# Manette.net
KiCad netlist of a schematic drawn in Altium Designer
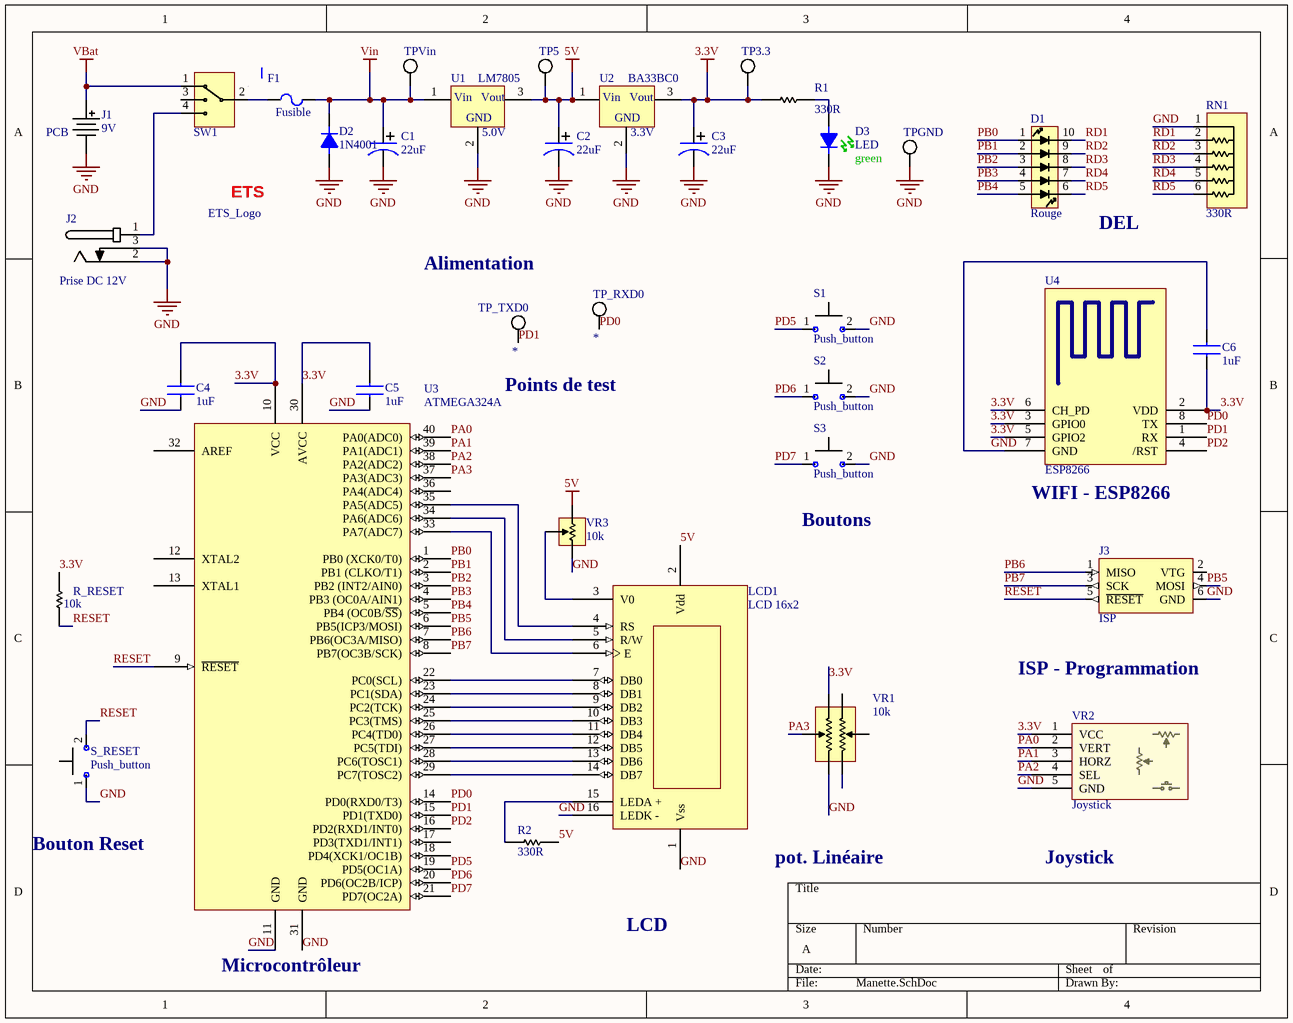
[diagram p0: Manette.SchDoc]

(export (version "E")
  (design (tool "Eeschema 10.0.6"))
  (components
    (comp (ref "C1")
      (value "22uF")
      (footprint "Cap Pol (100mil, 80mil)")
      (description "Capacitor")
      (libsource (lib "Condensateur") (part "Electrolytique"))
    )
    (comp (ref "C2")
      (value "22uF")
      (footprint "Cap Pol (100mil, 80mil)")
      (description "Capacitor")
      (libsource (lib "Condensateur") (part "Electrolytique"))
    )
    (comp (ref "C3")
      (value "22uF")
      (footprint "Cap Pol (100mil, 80mil)")
      (description "Capacitor")
      (libsource (lib "Condensateur") (part "Electrolytique"))
    )
    (comp (ref "C4")
      (value "1uF")
      (footprint "Cap UNPOL (200mil, 80mil)")
      (description "Capacitor")
      (libsource (lib "Condensateur") (part "Ceramique"))
    )
    (comp (ref "C5")
      (value "1uF")
      (footprint "Cap UNPOL (200mil, 80mil)")
      (description "Capacitor")
      (libsource (lib "Condensateur") (part "Ceramique"))
    )
    (comp (ref "C6")
      (value "1uF")
      (footprint "Cap UNPOL (200mil, 80mil)")
      (description "Capacitor")
      (libsource (lib "Condensateur") (part "Ceramique"))
    )
    (comp (ref "D1")
      (value "Rouge")
      (footprint "BARGRAPH 5 DEL")
      (description "Bargraph 5 DEL")
      (libsource (lib "DEL") (part "Bargraph 5 DEL"))
    )
    (comp (ref "D2")
      (value "1N4001")
      (footprint "DO-41 (AN) 400mil")
      (description "Diode 1N4001")
      (libsource (lib "Diode") (part "1N4001"))
    )
    (comp (ref "D3")
      (value "LED")
      (footprint "LED_GREEN_5mm-100mil")
      (description "DEL verte 5mm (translucide)")
      (fields (field (name "COLOR") "green"))
      (libsource (lib "DEL") (part "LED_verte"))
    )
    (comp (ref "F1") (value "Fuse") (footprint "Fuse") (libsource (lib "Fusible") (part "Fuse")))
    (comp (ref "J1")
      (value "9V")
      (footprint "9V PCB Through hole")
      (description "9V PCB battery holder through hole")
      (fields (field (name "Comment") "9 VPCB through hole"))
      (libsource (lib "Batterie") (part "9 VPCB through hole"))
    )
    (comp (ref "J2")
      (value "Prise DC 12V")
      (footprint "Prise DC 12V")
      (libsource (lib "PriseDC12V") (part "Prise DC 12V"))
    )
    (comp (ref "J3")
      (value "ISP")
      (footprint "ISP 2x3 avec detrompeur")
      (description "Connecteur ISP 2x3")
      (libsource (lib "Connecteur-Male") (part "ISP 2x3"))
    )
    (comp (ref "LCD1")
      (value "LCD 16x2")
      (footprint "LCD 16x2 sans socket")
      (description "Écran LCD compatible HD44780")
      (libsource (lib "Ecran LCD") (part "LCD 16x2"))
    )
    (comp (ref "R1")
      (value "330R")
      (footprint "Resistor 330 (400mils)")
      (description "Resistor 330R")
      (libsource (lib "Resistance") (part "Resistor 330R"))
    )
    (comp (ref "R2")
      (value "330R")
      (footprint "Resistor 330 (400mils)")
      (description "Resistor 330R")
      (libsource (lib "Resistance") (part "Resistor 330R"))
    )
    (comp (ref "RN1")
      (value "330R")
      (footprint "RESEAU 5 RESISTANCES")
      (description "Réseau de 5 résistances pour bus")
      (fields (field (name "Comment") "Réseau de 5 résistances"))
      (libsource (lib "Resistance") (part "Réseau de 5 résistances"))
    )
    (comp (ref "R_RESET")
      (value "10k")
      (footprint "Resistor 10k (400mils)")
      (description "Résistor 10k")
      (libsource (lib "Resistance") (part "Resistor 10k"))
    )
    (comp (ref "S1")
      (value "Push_button")
      (footprint "MJTP1230")
      (description "Bouton poussoir tactile")
      (libsource (lib "Interrupteur") (part "Push_button"))
    )
    (comp (ref "S2")
      (value "Push_button")
      (footprint "MJTP1230")
      (description "Bouton poussoir tactile")
      (libsource (lib "Interrupteur") (part "Push_button"))
    )
    (comp (ref "S3")
      (value "Push_button")
      (footprint "MJTP1230")
      (description "Bouton poussoir tactile")
      (libsource (lib "Interrupteur") (part "Push_button"))
    )
    (comp (ref "SS1") (value "ETS_Logo") (footprint "ETS-Logo") (libsource (lib "LogoETS") (part "ETS_Logo")))
    (comp (ref "SW1")
      (value "1825161-1")
      (footprint "1825161-1")
      (description "Interrupteur SP3T à glissière")
      (libsource (lib "Interrupteur") (part "1825161-1"))
    )
    (comp (ref "S_RESET")
      (value "Push_button")
      (footprint "MJTP1230")
      (description "Bouton poussoir tactile")
      (libsource (lib "Interrupteur") (part "Push_button"))
    )
    (comp (ref "TP3.3")
      (value "*")
      (footprint "HEADER MALE 1X1")
      (description "Point de test")
      (libsource (lib "Connecteur-Male") (part "Test point"))
    )
    (comp (ref "TP5")
      (value "*")
      (footprint "HEADER MALE 1X1")
      (description "Point de test")
      (libsource (lib "Connecteur-Male") (part "Test point"))
    )
    (comp (ref "TPGND")
      (value "*")
      (footprint "HEADER MALE 1X1")
      (description "Point de test")
      (libsource (lib "Connecteur-Male") (part "Test point"))
    )
    (comp (ref "TPVin")
      (value "*")
      (footprint "HEADER MALE 1X1")
      (description "Point de test")
      (libsource (lib "Connecteur-Male") (part "Test point"))
    )
    (comp (ref "TP_RXD0")
      (value "*")
      (footprint "HEADER MALE 1X1")
      (description "Point de test")
      (fields (field (name "ALTIUM_VALUE") "*"))
      (libsource (lib "Connecteur-Male") (part "Test point"))
    )
    (comp (ref "TP_TXD0")
      (value "*")
      (footprint "HEADER MALE 1X1")
      (description "Point de test")
      (fields (field (name "ALTIUM_VALUE") "*"))
      (libsource (lib "Connecteur-Male") (part "Test point"))
    )
    (comp (ref "U1")
      (value "LM7805")
      (footprint "TO-220FP-3")
      (description "Régulateur de tension 5V")
      (libsource (lib "Convertisseur Tension") (part "LM7805"))
    )
    (comp (ref "U2")
      (value "BA33BC0")
      (footprint "TO-220FP-3")
      (description "LDO 3.3V, 1A, 0.3V@200mA, up to 16V (BA33BC0)")
      (libsource (lib "Convertisseur Tension") (part "LDO 3.3V"))
    )
    (comp (ref "U3")
      (value "ATMEGA324A")
      (footprint "ATMEGA324A-DIP")
      (description "Microcontrôleur ATmega324A avec 32K de flash")
      (libsource (lib "Microcontroleur") (part "ATMEGA324A"))
    )
    (comp (ref "U4") (value "ESP8266") (footprint "ESP8266") (libsource (lib "ESP8266") (part "ESP8266")))
    (comp (ref "VR1")
      (value "10k")
      (footprint "PS45M-0MC2BR10KN")
      (description "Potentiomètre à glissière double 10k")
      (libsource (lib "Potentiometre") (part "PS45M-0MC2BR10KN"))
    )
    (comp (ref "VR2")
      (value "Joystick")
      (footprint "JOYSTICK SUR BREAKOUT&SOCKET")
      (description "2 axes thumb joystick avec bouton")
      (libsource (lib "Joystick") (part "Joystick"))
    )
    (comp (ref "VR3")
      (value "10k")
      (footprint "Trimpot")
      (description "Potentiomètre linéaire")
      (fields (field (name "Comment") "Trimpot"))
      (libsource (lib "Potentiometre") (part "Trimpot"))
    )
  )
  (nets
    (net (code "1") (name "/PA0") (class "Default")
      (node (ref "U3") (pin "40") (pinfunction "PA0(ADC0)_40") (pintype "bidirectional"))
      (node (ref "VR2") (pin "2") (pinfunction "VERT_2") (pintype "passive"))
    )
    (net (code "2") (name "/PA1") (class "Default")
      (node (ref "U3") (pin "39") (pinfunction "PA1(ADC1)_39") (pintype "bidirectional"))
      (node (ref "VR2") (pin "3") (pinfunction "HORZ_3") (pintype "passive"))
    )
    (net (code "3") (name "/PA2") (class "Default")
      (node (ref "U3") (pin "38") (pinfunction "PA2(ADC2)_38") (pintype "bidirectional"))
      (node (ref "VR2") (pin "4") (pinfunction "SEL_4") (pintype "passive"))
    )
    (net (code "4") (name "/PA3") (class "Default")
      (node (ref "U3") (pin "37") (pinfunction "PA3(ADC3)_37") (pintype "bidirectional"))
      (node (ref "VR1") (pin "2") (pinfunction "V_2") (pintype "passive"))
    )
    (net (code "5") (name "/PB0") (class "Default")
      (node (ref "D1") (pin "1") (pinfunction "A1_1") (pintype "passive"))
      (node (ref "U3") (pin "1") (pinfunction "PB0_(XCK0/T0)_1") (pintype "bidirectional"))
    )
    (net (code "6") (name "/PB1") (class "Default")
      (node (ref "D1") (pin "2") (pinfunction "A2_2") (pintype "passive"))
      (node (ref "U3") (pin "2") (pinfunction "PB1_(CLKO/T1)_2") (pintype "bidirectional"))
    )
    (net (code "7") (name "/PB2") (class "Default")
      (node (ref "D1") (pin "3") (pinfunction "A3_3") (pintype "passive"))
      (node (ref "U3") (pin "3") (pinfunction "PB2_(INT2/AIN0)_3") (pintype "bidirectional"))
    )
    (net (code "8") (name "/PB3") (class "Default")
      (node (ref "D1") (pin "4") (pinfunction "A4_4") (pintype "passive"))
      (node (ref "U3") (pin "4") (pinfunction "PB3_(OC0A/AIN1)_4") (pintype "bidirectional"))
    )
    (net (code "9") (name "/PB4") (class "Default")
      (node (ref "D1") (pin "5") (pinfunction "A5_5") (pintype "passive"))
      (node (ref "U3") (pin "5") (pinfunction "PB4_(OC0B/~{SS})_5") (pintype "bidirectional"))
    )
    (net (code "10") (name "/PB5") (class "Default")
      (node (ref "J3") (pin "4") (pinfunction "MOSI_4") (pintype "output"))
      (node (ref "U3") (pin "6") (pinfunction "PB5(ICP3/MOSI)_6") (pintype "bidirectional"))
    )
    (net (code "11") (name "/PB6") (class "Default")
      (node (ref "J3") (pin "1") (pinfunction "MISO_1") (pintype "input"))
      (node (ref "U3") (pin "7") (pinfunction "PB6(OC3A/MISO)_7") (pintype "bidirectional"))
    )
    (net (code "12") (name "/PB7") (class "Default")
      (node (ref "J3") (pin "3") (pinfunction "SCK_3") (pintype "output"))
      (node (ref "U3") (pin "8") (pinfunction "PB7(OC3B/SCK)_8") (pintype "bidirectional"))
    )
    (net (code "13") (name "/PD0") (class "Default")
      (node (ref "TP_RXD0") (pin "1") (pinfunction "1_1") (pintype "passive"))
      (node (ref "U3") (pin "14") (pinfunction "PD0(RXD0/T3)_14") (pintype "bidirectional"))
      (node (ref "U4") (pin "8") (pinfunction "TX_8") (pintype "passive"))
    )
    (net (code "14") (name "/PD1") (class "Default")
      (node (ref "TP_TXD0") (pin "1") (pinfunction "1_1") (pintype "passive"))
      (node (ref "U3") (pin "15") (pinfunction "PD1(TXD0)_15") (pintype "bidirectional"))
      (node (ref "U4") (pin "1") (pinfunction "RX_1") (pintype "passive"))
    )
    (net (code "15") (name "/PD2") (class "Default")
      (node (ref "U3") (pin "16") (pinfunction "PD2(RXD1/INT0)_16") (pintype "bidirectional"))
      (node (ref "U4") (pin "4") (pinfunction "/RST_4") (pintype "passive"))
    )
    (net (code "16") (name "/PD5") (class "Default")
      (node (ref "S1") (pin "1") (pintype "passive"))
      (node (ref "U3") (pin "19") (pinfunction "PD5(OC1A)_19") (pintype "bidirectional"))
    )
    (net (code "17") (name "/PD6") (class "Default")
      (node (ref "S2") (pin "1") (pintype "passive"))
      (node (ref "U3") (pin "20") (pinfunction "PD6(OC2B/ICP)_20") (pintype "bidirectional"))
    )
    (net (code "18") (name "/PD7") (class "Default")
      (node (ref "S3") (pin "1") (pintype "passive"))
      (node (ref "U3") (pin "21") (pinfunction "PD7(OC2A)_21") (pintype "bidirectional"))
    )
    (net (code "19") (name "/RD1") (class "Default")
      (node (ref "D1") (pin "10") (pinfunction "K1_10") (pintype "passive"))
      (node (ref "RN1") (pin "2") (pinfunction "R1_2") (pintype "passive"))
    )
    (net (code "20") (name "/RD2") (class "Default")
      (node (ref "D1") (pin "9") (pinfunction "K2_9") (pintype "passive"))
      (node (ref "RN1") (pin "3") (pinfunction "R2_3") (pintype "passive"))
    )
    (net (code "21") (name "/RD3") (class "Default")
      (node (ref "D1") (pin "8") (pinfunction "K3_8") (pintype "passive"))
      (node (ref "RN1") (pin "4") (pinfunction "R3_4") (pintype "passive"))
    )
    (net (code "22") (name "/RD4") (class "Default")
      (node (ref "D1") (pin "7") (pinfunction "K4_7") (pintype "passive"))
      (node (ref "RN1") (pin "5") (pinfunction "R4_5") (pintype "passive"))
    )
    (net (code "23") (name "/RD5") (class "Default")
      (node (ref "D1") (pin "6") (pinfunction "K5_6") (pintype "passive"))
      (node (ref "RN1") (pin "6") (pinfunction "R5_6") (pintype "passive"))
    )
    (net (code "24") (name "/RESET") (class "Default")
      (node (ref "J3") (pin "5") (pinfunction "~{RESET}_5") (pintype "output"))
      (node (ref "R_RESET") (pin "1") (pinfunction "1_1") (pintype "passive"))
      (node (ref "S_RESET") (pin "2") (pintype "passive"))
      (node (ref "U3") (pin "9") (pinfunction "~{RESET}_9") (pintype "input"))
    )
    (net (code "25") (name "3.3V") (class "Default")
      (node (ref "C3") (pin "2") (pinfunction "pos_2") (pintype "passive"))
      (node (ref "C4") (pin "2") (pinfunction "2_2") (pintype "passive"))
      (node (ref "C5") (pin "2") (pinfunction "2_2") (pintype "passive"))
      (node (ref "C6") (pin "1") (pinfunction "1_1") (pintype "passive"))
      (node (ref "R1") (pin "2") (pinfunction "2_2") (pintype "passive"))
      (node (ref "R_RESET") (pin "2") (pinfunction "2_2") (pintype "passive"))
      (node (ref "TP3.3") (pin "1") (pinfunction "1_1") (pintype "passive"))
      (node (ref "U2") (pin "3") (pinfunction "VOUT_3") (pintype "passive"))
      (node (ref "U3") (pin "10") (pinfunction "VCC_10") (pintype "power_in"))
      (node (ref "U3") (pin "30") (pinfunction "AVCC_30") (pintype "power_in"))
      (node (ref "U4") (pin "2") (pinfunction "VDD_2") (pintype "passive"))
      (node (ref "U4") (pin "3") (pinfunction "GPIO0_3") (pintype "passive"))
      (node (ref "U4") (pin "5") (pinfunction "GPIO2_5") (pintype "passive"))
      (node (ref "U4") (pin "6") (pinfunction "CH_PD_6") (pintype "passive"))
      (node (ref "VR1") (pin "1") (pinfunction "V_HI_1") (pintype "passive"))
      (node (ref "VR2") (pin "1") (pinfunction "VCC_1") (pintype "power_in"))
    )
    (net (code "26") (name "5V") (class "Default")
      (node (ref "C2") (pin "2") (pinfunction "pos_2") (pintype "passive"))
      (node (ref "LCD1") (pin "2") (pinfunction "Vdd_2") (pintype "power_in"))
      (node (ref "R2") (pin "2") (pinfunction "2_2") (pintype "passive"))
      (node (ref "TP5") (pin "1") (pinfunction "1_1") (pintype "passive"))
      (node (ref "U1") (pin "3") (pinfunction "VOUT_3") (pintype "passive"))
      (node (ref "U2") (pin "1") (pinfunction "VCC_1") (pintype "passive"))
      (node (ref "VR3") (pin "1") (pinfunction "V_HI_1") (pintype "passive"))
    )
    (net (code "27") (name "GND") (class "Default")
      (node (ref "C1") (pin "1") (pinfunction "neg_1") (pintype "passive"))
      (node (ref "C2") (pin "1") (pinfunction "neg_1") (pintype "passive"))
      (node (ref "C3") (pin "1") (pinfunction "neg_1") (pintype "passive"))
      (node (ref "C4") (pin "1") (pinfunction "1_1") (pintype "passive"))
      (node (ref "C5") (pin "1") (pinfunction "1_1") (pintype "passive"))
      (node (ref "C6") (pin "2") (pinfunction "2_2") (pintype "passive"))
      (node (ref "D2") (pin "1") (pinfunction "A_1") (pintype "passive"))
      (node (ref "D3") (pin "2") (pinfunction "K_2") (pintype "passive"))
      (node (ref "J1") (pin "2") (pinfunction "NEG_2") (pintype "passive"))
      (node (ref "J2") (pin "2") (pinfunction "NEG_2") (pintype "passive"))
      (node (ref "J2") (pin "3") (pinfunction "NEG/NC_3") (pintype "passive"))
      (node (ref "J3") (pin "6") (pinfunction "GND_6") (pintype "power_in"))
      (node (ref "LCD1") (pin "1") (pinfunction "Vss_1") (pintype "power_in"))
      (node (ref "LCD1") (pin "16") (pinfunction "LEDK_-_16") (pintype "passive"))
      (node (ref "RN1") (pin "1") (pinfunction "COM_1") (pintype "passive"))
      (node (ref "S1") (pin "2") (pintype "passive"))
      (node (ref "S2") (pin "2") (pintype "passive"))
      (node (ref "S3") (pin "2") (pintype "passive"))
      (node (ref "S_RESET") (pin "1") (pintype "passive"))
      (node (ref "TPGND") (pin "1") (pinfunction "1_1") (pintype "passive"))
      (node (ref "U1") (pin "2") (pinfunction "GND_2") (pintype "passive"))
      (node (ref "U2") (pin "2") (pinfunction "GND_2") (pintype "passive"))
      (node (ref "U3") (pin "11") (pinfunction "GND_11") (pintype "power_in"))
      (node (ref "U3") (pin "31") (pinfunction "GND_31") (pintype "power_in"))
      (node (ref "U4") (pin "7") (pinfunction "GND_7") (pintype "passive"))
      (node (ref "VR1") (pin "3") (pinfunction "V_LOW_3") (pintype "passive"))
      (node (ref "VR2") (pin "5") (pinfunction "GND_5") (pintype "passive"))
      (node (ref "VR3") (pin "3") (pinfunction "V_LOW_3") (pintype "passive"))
    )
    (net (code "28") (name "Net-(D3-A)") (class "Default")
      (node (ref "D3") (pin "1") (pinfunction "A_1") (pintype "passive"))
      (node (ref "R1") (pin "1") (pinfunction "1_1") (pintype "passive"))
    )
    (net (code "29") (name "Net-(F1-Pad1)") (class "Default")
      (node (ref "F1") (pin "1") (pinfunction "1_1") (pintype "passive"))
      (node (ref "SW1") (pin "2") (pinfunction "2_2") (pintype "passive"))
    )
    (net (code "30") (name "Net-(J2-POS)") (class "Default")
      (node (ref "J2") (pin "1") (pinfunction "POS_1") (pintype "passive"))
      (node (ref "SW1") (pin "4") (pinfunction "4_4") (pintype "passive"))
    )
    (net (code "31") (name "Net-(LCD1-DB0)") (class "Default")
      (node (ref "LCD1") (pin "7") (pinfunction "DB0_7") (pintype "bidirectional"))
      (node (ref "U3") (pin "22") (pinfunction "PC0(SCL)_22") (pintype "bidirectional"))
    )
    (net (code "32") (name "Net-(LCD1-DB1)") (class "Default")
      (node (ref "LCD1") (pin "8") (pinfunction "DB1_8") (pintype "bidirectional"))
      (node (ref "U3") (pin "23") (pinfunction "PC1(SDA)_23") (pintype "bidirectional"))
    )
    (net (code "33") (name "Net-(LCD1-DB2)") (class "Default")
      (node (ref "LCD1") (pin "9") (pinfunction "DB2_9") (pintype "bidirectional"))
      (node (ref "U3") (pin "24") (pinfunction "PC2(TCK)_24") (pintype "bidirectional"))
    )
    (net (code "34") (name "Net-(LCD1-DB3)") (class "Default")
      (node (ref "LCD1") (pin "10") (pinfunction "DB3_10") (pintype "bidirectional"))
      (node (ref "U3") (pin "25") (pinfunction "PC3(TMS)_25") (pintype "bidirectional"))
    )
    (net (code "35") (name "Net-(LCD1-DB4)") (class "Default")
      (node (ref "LCD1") (pin "11") (pinfunction "DB4_11") (pintype "bidirectional"))
      (node (ref "U3") (pin "26") (pinfunction "PC4(TD0)_26") (pintype "bidirectional"))
    )
    (net (code "36") (name "Net-(LCD1-DB5)") (class "Default")
      (node (ref "LCD1") (pin "12") (pinfunction "DB5_12") (pintype "bidirectional"))
      (node (ref "U3") (pin "27") (pinfunction "PC5(TDI)_27") (pintype "bidirectional"))
    )
    (net (code "37") (name "Net-(LCD1-DB6)") (class "Default")
      (node (ref "LCD1") (pin "13") (pinfunction "DB6_13") (pintype "bidirectional"))
      (node (ref "U3") (pin "28") (pinfunction "PC6(TOSC1)_28") (pintype "bidirectional"))
    )
    (net (code "38") (name "Net-(LCD1-DB7)") (class "Default")
      (node (ref "LCD1") (pin "14") (pinfunction "DB7_14") (pintype "bidirectional"))
      (node (ref "U3") (pin "29") (pinfunction "PC7(TOSC2)_29") (pintype "bidirectional"))
    )
    (net (code "39") (name "Net-(LCD1-E)") (class "Default")
      (node (ref "LCD1") (pin "6") (pinfunction "E_6") (pintype "input"))
      (node (ref "U3") (pin "33") (pinfunction "PA7(ADC7)_33") (pintype "bidirectional"))
    )
    (net (code "40") (name "Net-(LCD1-LEDA_+)") (class "Default")
      (node (ref "LCD1") (pin "15") (pinfunction "LEDA_+_15") (pintype "passive"))
      (node (ref "R2") (pin "1") (pinfunction "1_1") (pintype "passive"))
    )
    (net (code "41") (name "Net-(LCD1-RS)") (class "Default")
      (node (ref "LCD1") (pin "4") (pinfunction "RS_4") (pintype "input"))
      (node (ref "U3") (pin "35") (pinfunction "PA5(ADC5)_35") (pintype "bidirectional"))
    )
    (net (code "42") (name "Net-(LCD1-R{slash}W)") (class "Default")
      (node (ref "LCD1") (pin "5") (pinfunction "R/W_5") (pintype "input"))
      (node (ref "U3") (pin "34") (pinfunction "PA6(ADC6)_34") (pintype "bidirectional"))
    )
    (net (code "43") (name "Net-(LCD1-V0)") (class "Default")
      (node (ref "LCD1") (pin "3") (pinfunction "V0_3") (pintype "passive"))
      (node (ref "VR3") (pin "2") (pinfunction "V_2") (pintype "passive"))
    )
    (net (code "44") (name "VBat") (class "Default")
      (node (ref "J1") (pin "1") (pinfunction "POS_1") (pintype "passive"))
      (node (ref "SW1") (pin "1") (pinfunction "1_1") (pintype "passive"))
    )
    (net (code "45") (name "Vin") (class "Default")
      (node (ref "C1") (pin "2") (pinfunction "pos_2") (pintype "passive"))
      (node (ref "D2") (pin "2") (pinfunction "K_2") (pintype "passive"))
      (node (ref "F1") (pin "2") (pinfunction "2_2") (pintype "passive"))
      (node (ref "TPVin") (pin "1") (pinfunction "1_1") (pintype "passive"))
      (node (ref "U1") (pin "1") (pinfunction "VCC_1") (pintype "passive"))
    )
    (net (code "46") (name "unconnected-(J3-VTG-Pad2)") (class "Default")
      (node (ref "J3") (pin "2") (pinfunction "VTG_2") (pintype "power_in"))
    )
    (net (code "47") (name "unconnected-(SW1-Pad3)") (class "Default")
      (node (ref "SW1") (pin "3") (pinfunction "3_3") (pintype "passive"))
    )
    (net (code "48") (name "unconnected-(U3-AREF-Pad32)") (class "Default")
      (node (ref "U3") (pin "32") (pinfunction "AREF_32") (pintype "passive"))
    )
    (net (code "49") (name "unconnected-(U3-PA4(ADC4)-Pad36)") (class "Default")
      (node (ref "U3") (pin "36") (pinfunction "PA4(ADC4)_36") (pintype "bidirectional"))
    )
    (net (code "50") (name "unconnected-(U3-PD3(TXD1{slash}INT1)-Pad17)") (class "Default")
      (node (ref "U3") (pin "17") (pinfunction "PD3(TXD1/INT1)_17") (pintype "bidirectional"))
    )
    (net (code "51") (name "unconnected-(U3-PD4(XCK1{slash}OC1B)-Pad18)") (class "Default")
      (node (ref "U3") (pin "18") (pinfunction "PD4(XCK1/OC1B)_18") (pintype "bidirectional"))
    )
    (net (code "52") (name "unconnected-(U3-XTAL1-Pad13)") (class "Default")
      (node (ref "U3") (pin "13") (pinfunction "XTAL1_13") (pintype "passive"))
    )
    (net (code "53") (name "unconnected-(U3-XTAL2-Pad12)") (class "Default")
      (node (ref "U3") (pin "12") (pinfunction "XTAL2_12") (pintype "passive"))
    )
    (net (code "54") (name "unconnected-(VR1-H-Pad5)") (class "Default")
      (node (ref "VR1") (pin "5") (pinfunction "H_5") (pintype "passive"))
    )
    (net (code "55") (name "unconnected-(VR1-H_HI-Pad4)") (class "Default")
      (node (ref "VR1") (pin "4") (pinfunction "H_HI_4") (pintype "passive"))
    )
    (net (code "56") (name "unconnected-(VR1-H_LOW-Pad6)") (class "Default")
      (node (ref "VR1") (pin "6") (pinfunction "H_LOW_6") (pintype "passive"))
    )
  )
)
